# Adafruit_PCA9685_rev_C.net
KiCad netlist of a schematic drawn in EAGLE
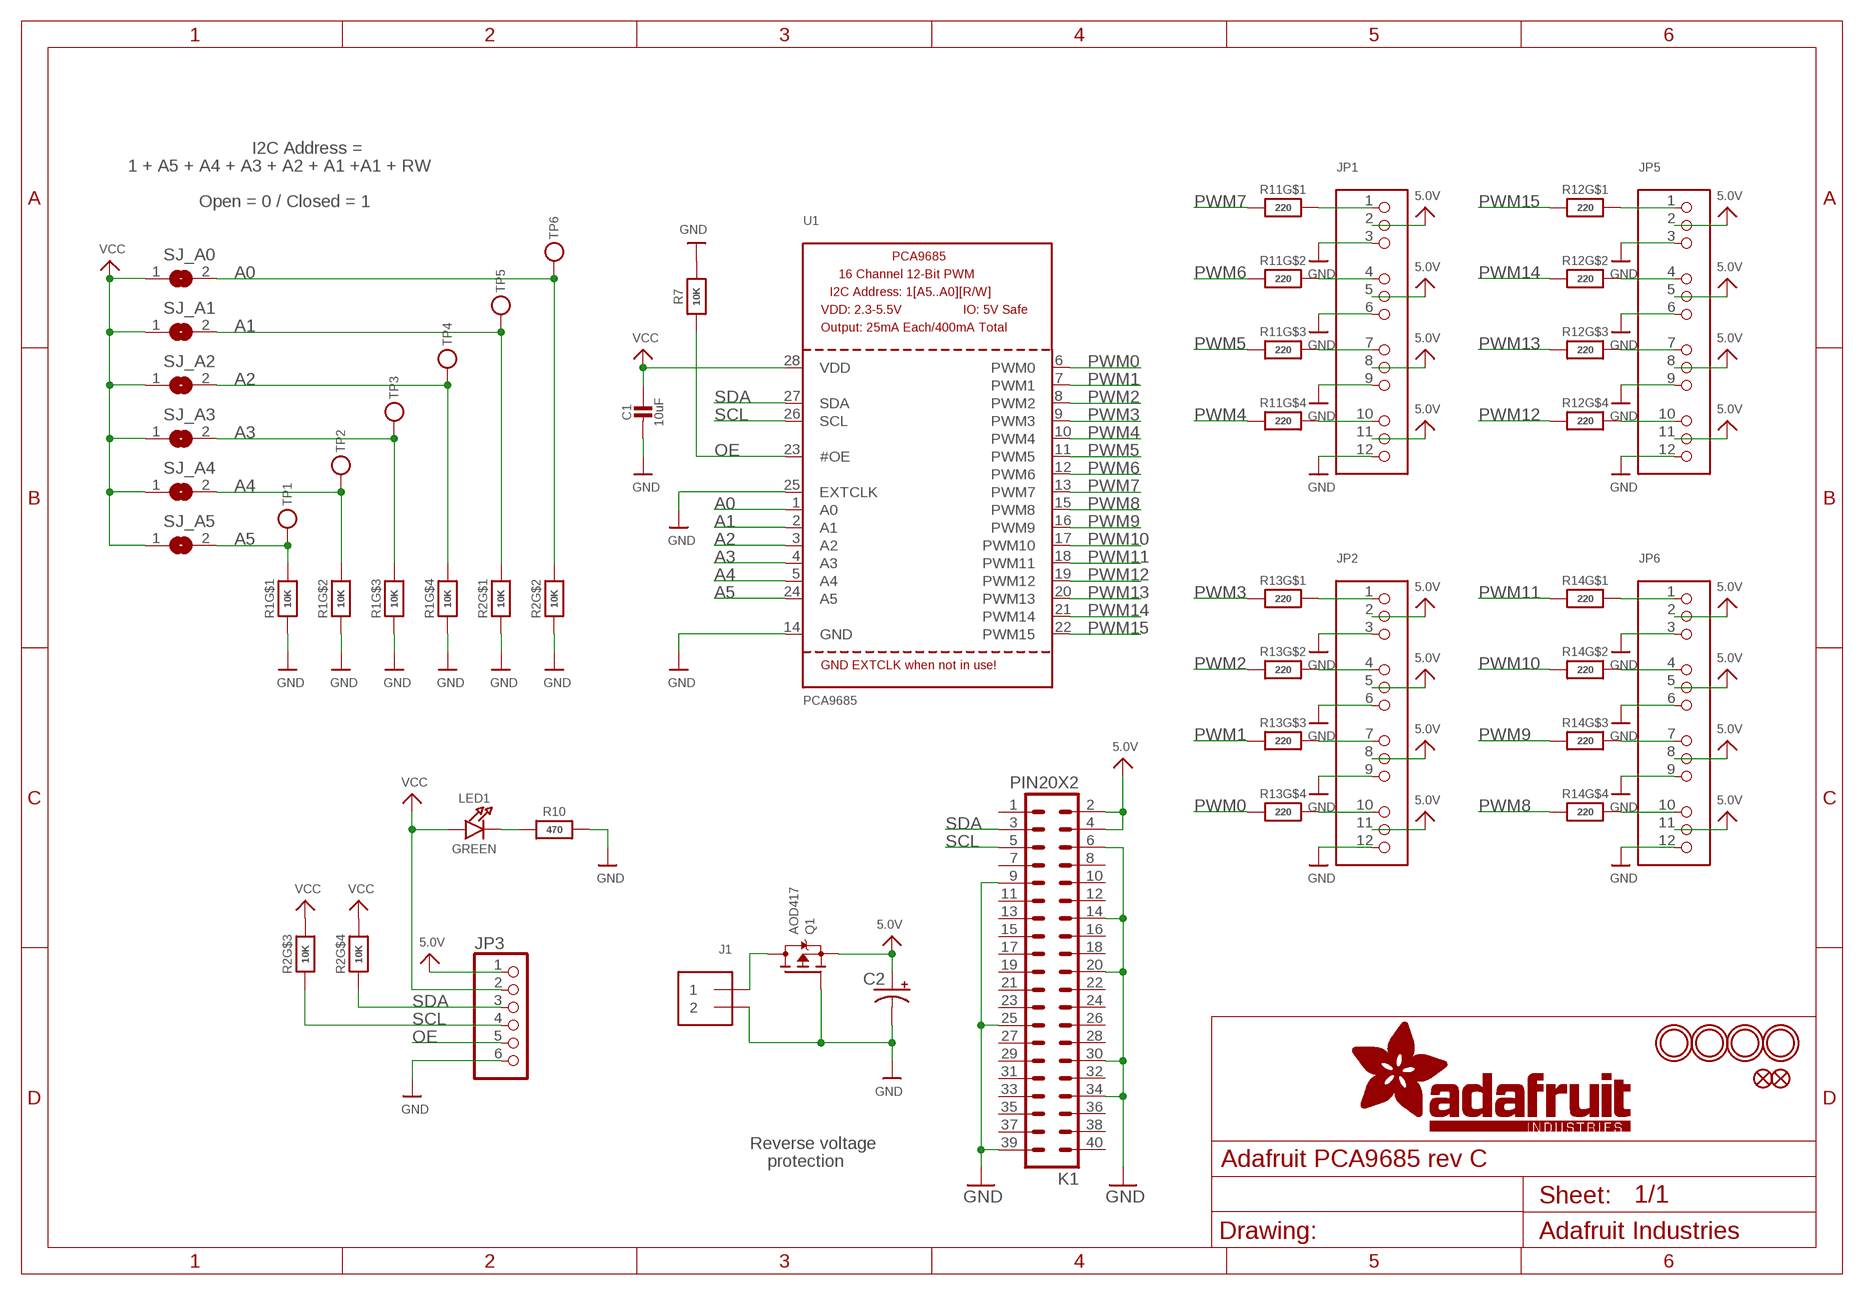
[diagram p0: schematic, sheet 1]

(export (version "E")
  (design (tool "Eeschema 10.0.6"))
  (components
    (comp (ref "C1")
      (value "10uF")
      (footprint "eagle-import:0805-NO")
      (libsource (lib "eagle-import") (part "CAP_CERAMIC0805-NOOUTLINE"))
    )
    (comp (ref "C2")
      (value "CPOL-USE3.5-8")
      (footprint "eagle-import:E3,5-8")
      (libsource (lib "eagle-import") (part "CPOL-USE3.5-8"))
    )
    (comp (ref "FID1")
      (value "FIDUCIAL\"\"")
      (footprint "eagle-import:FIDUCIAL_1MM")
      (libsource (lib "eagle-import") (part "FIDUCIAL{dblquote}{dblquote}"))
    )
    (comp (ref "FID2")
      (value "FIDUCIAL\"\"")
      (footprint "eagle-import:FIDUCIAL_1MM")
      (libsource (lib "eagle-import") (part "FIDUCIAL{dblquote}{dblquote}"))
    )
    (comp (ref "J1")
      (value "TERMBLOCK_1X2")
      (footprint "eagle-import:TERMBLOCK_1X2-3.5MM")
      (libsource (lib "eagle-import") (part "TERMBLOCK_1X2"))
    )
    (comp (ref "JP1")
      (value "HEADER-3X04")
      (footprint "eagle-import:3X04")
      (libsource (lib "eagle-import") (part "HEADER-3X04"))
    )
    (comp (ref "JP2")
      (value "HEADER-3X04")
      (footprint "eagle-import:3X04")
      (libsource (lib "eagle-import") (part "HEADER-3X04"))
    )
    (comp (ref "JP3")
      (value "PINHD-1X6CB")
      (footprint "eagle-import:1X06-CLEANBIG")
      (libsource (lib "eagle-import") (part "PINHD-1X6CB"))
    )
    (comp (ref "JP5")
      (value "HEADER-3X04")
      (footprint "eagle-import:3X04")
      (libsource (lib "eagle-import") (part "HEADER-3X04"))
    )
    (comp (ref "JP6")
      (value "HEADER-3X04")
      (footprint "eagle-import:3X04")
      (libsource (lib "eagle-import") (part "HEADER-3X04"))
    )
    (comp (ref "K1")
      (value "PIN20X2")
      (footprint "eagle-import:PIN_20X2")
      (libsource (lib "eagle-import") (part "PIN20X2"))
    )
    (comp (ref "LED1")
      (value "GREEN")
      (footprint "eagle-import:CHIPLED_0805_NOOUTLINE")
      (libsource (lib "eagle-import") (part "LED0805_NOOUTLINE"))
    )
    (comp (ref "Q1")
      (value "AOD417")
      (footprint "eagle-import:TO252")
      (libsource (lib "eagle-import") (part "MOSFET-PTO252"))
    )
    (comp (ref "R1")
      (value "10K")
      (footprint "eagle-import:RESPACK_4X0603")
      (libsource (lib "eagle-import") (part "RESISTOR_4PACK"))
    )
    (comp (ref "R2")
      (value "10K")
      (footprint "eagle-import:RESPACK_4X0603")
      (libsource (lib "eagle-import") (part "RESISTOR_4PACK"))
    )
    (comp (ref "R7")
      (value "10K")
      (footprint "eagle-import:0805-NO")
      (libsource (lib "eagle-import") (part "RESISTOR0805_NOOUTLINE"))
    )
    (comp (ref "R10")
      (value "470")
      (footprint "eagle-import:_0805MP")
      (libsource (lib "eagle-import") (part "RESISTOR_0805MP"))
    )
    (comp (ref "R11")
      (value "220")
      (footprint "eagle-import:RESPACK_4X0603")
      (libsource (lib "eagle-import") (part "RESISTOR_4PACK"))
    )
    (comp (ref "R12")
      (value "220")
      (footprint "eagle-import:RESPACK_4X0603")
      (libsource (lib "eagle-import") (part "RESISTOR_4PACK"))
    )
    (comp (ref "R13")
      (value "220")
      (footprint "eagle-import:RESPACK_4X0603")
      (libsource (lib "eagle-import") (part "RESISTOR_4PACK"))
    )
    (comp (ref "R14")
      (value "220")
      (footprint "eagle-import:RESPACK_4X0603")
      (libsource (lib "eagle-import") (part "RESISTOR_4PACK"))
    )
    (comp (ref "SJ_A0")
      (value "SOLDERJUMPERREFLOW_NOPASTE")
      (footprint "eagle-import:SOLDERJUMPER_REFLOW_NOPASTE")
      (libsource (lib "eagle-import") (part "SOLDERJUMPERREFLOW_NOPASTE"))
    )
    (comp (ref "SJ_A1")
      (value "SOLDERJUMPERREFLOW_NOPASTE")
      (footprint "eagle-import:SOLDERJUMPER_REFLOW_NOPASTE")
      (libsource (lib "eagle-import") (part "SOLDERJUMPERREFLOW_NOPASTE"))
    )
    (comp (ref "SJ_A2")
      (value "SOLDERJUMPERREFLOW_NOPASTE")
      (footprint "eagle-import:SOLDERJUMPER_REFLOW_NOPASTE")
      (libsource (lib "eagle-import") (part "SOLDERJUMPERREFLOW_NOPASTE"))
    )
    (comp (ref "SJ_A3")
      (value "SOLDERJUMPERREFLOW_NOPASTE")
      (footprint "eagle-import:SOLDERJUMPER_REFLOW_NOPASTE")
      (libsource (lib "eagle-import") (part "SOLDERJUMPERREFLOW_NOPASTE"))
    )
    (comp (ref "SJ_A4")
      (value "SOLDERJUMPERREFLOW_NOPASTE")
      (footprint "eagle-import:SOLDERJUMPER_REFLOW_NOPASTE")
      (libsource (lib "eagle-import") (part "SOLDERJUMPERREFLOW_NOPASTE"))
    )
    (comp (ref "SJ_A5")
      (value "SOLDERJUMPERREFLOW_NOPASTE")
      (footprint "eagle-import:SOLDERJUMPER_REFLOW_NOPASTE")
      (libsource (lib "eagle-import") (part "SOLDERJUMPERREFLOW_NOPASTE"))
    )
    (comp (ref "TP1")
      (value "TESTPOINTROUND1MM")
      (footprint "eagle-import:TESTPOINT_ROUND_1MM")
      (libsource (lib "eagle-import") (part "TESTPOINTROUND1MM"))
    )
    (comp (ref "TP2")
      (value "TESTPOINTROUND1MM")
      (footprint "eagle-import:TESTPOINT_ROUND_1MM")
      (libsource (lib "eagle-import") (part "TESTPOINTROUND1MM"))
    )
    (comp (ref "TP3")
      (value "TESTPOINTROUND1MM")
      (footprint "eagle-import:TESTPOINT_ROUND_1MM")
      (libsource (lib "eagle-import") (part "TESTPOINTROUND1MM"))
    )
    (comp (ref "TP4")
      (value "TESTPOINTROUND1MM")
      (footprint "eagle-import:TESTPOINT_ROUND_1MM")
      (libsource (lib "eagle-import") (part "TESTPOINTROUND1MM"))
    )
    (comp (ref "TP5")
      (value "TESTPOINTROUND1MM")
      (footprint "eagle-import:TESTPOINT_ROUND_1MM")
      (libsource (lib "eagle-import") (part "TESTPOINTROUND1MM"))
    )
    (comp (ref "TP6")
      (value "TESTPOINTROUND1MM")
      (footprint "eagle-import:TESTPOINT_ROUND_1MM")
      (libsource (lib "eagle-import") (part "TESTPOINTROUND1MM"))
    )
    (comp (ref "U$47")
      (value "MOUNTINGHOLE2.5")
      (footprint "eagle-import:MOUNTINGHOLE_2.5_PLATED")
      (libsource (lib "eagle-import") (part "MOUNTINGHOLE2.5"))
    )
    (comp (ref "U$48")
      (value "MOUNTINGHOLE2.5")
      (footprint "eagle-import:MOUNTINGHOLE_2.5_PLATED")
      (libsource (lib "eagle-import") (part "MOUNTINGHOLE2.5"))
    )
    (comp (ref "U$49")
      (value "MOUNTINGHOLE2.5")
      (footprint "eagle-import:MOUNTINGHOLE_2.5_PLATED")
      (libsource (lib "eagle-import") (part "MOUNTINGHOLE2.5"))
    )
    (comp (ref "U$50")
      (value "MOUNTINGHOLE2.5")
      (footprint "eagle-import:MOUNTINGHOLE_2.5_PLATED")
      (libsource (lib "eagle-import") (part "MOUNTINGHOLE2.5"))
    )
    (comp (ref "U1")
      (value "PCA9685")
      (footprint "eagle-import:TSSOP28")
      (libsource (lib "eagle-import") (part "PCA9685"))
    )
  )
  (nets
    (net (code "1") (name "/A0") (class "Default")
      (node (ref "R2") (pin "7") (pinfunction "2_7") (pintype "passive"))
      (node (ref "SJ_A0") (pin "2") (pinfunction "2_2") (pintype "passive"))
      (node (ref "TP6") (pin "P$1") (pinfunction "P$1_P$1") (pintype "bidirectional"))
      (node (ref "U1") (pin "1") (pinfunction "A0_1") (pintype "bidirectional"))
    )
    (net (code "2") (name "/A1") (class "Default")
      (node (ref "R2") (pin "8") (pinfunction "2_8") (pintype "passive"))
      (node (ref "SJ_A1") (pin "2") (pinfunction "2_2") (pintype "passive"))
      (node (ref "TP5") (pin "P$1") (pinfunction "P$1_P$1") (pintype "bidirectional"))
      (node (ref "U1") (pin "2") (pinfunction "A1_2") (pintype "bidirectional"))
    )
    (net (code "3") (name "/A2") (class "Default")
      (node (ref "R1") (pin "5") (pinfunction "2_5") (pintype "passive"))
      (node (ref "SJ_A2") (pin "2") (pinfunction "2_2") (pintype "passive"))
      (node (ref "TP4") (pin "P$1") (pinfunction "P$1_P$1") (pintype "bidirectional"))
      (node (ref "U1") (pin "3") (pinfunction "A2_3") (pintype "bidirectional"))
    )
    (net (code "4") (name "/A3") (class "Default")
      (node (ref "R1") (pin "6") (pinfunction "2_6") (pintype "passive"))
      (node (ref "SJ_A3") (pin "2") (pinfunction "2_2") (pintype "passive"))
      (node (ref "TP3") (pin "P$1") (pinfunction "P$1_P$1") (pintype "bidirectional"))
      (node (ref "U1") (pin "4") (pinfunction "A3_4") (pintype "bidirectional"))
    )
    (net (code "5") (name "/A4") (class "Default")
      (node (ref "R1") (pin "7") (pinfunction "2_7") (pintype "passive"))
      (node (ref "SJ_A4") (pin "2") (pinfunction "2_2") (pintype "passive"))
      (node (ref "TP2") (pin "P$1") (pinfunction "P$1_P$1") (pintype "bidirectional"))
      (node (ref "U1") (pin "5") (pinfunction "A4_5") (pintype "bidirectional"))
    )
    (net (code "6") (name "/A5") (class "Default")
      (node (ref "R1") (pin "8") (pinfunction "2_8") (pintype "passive"))
      (node (ref "SJ_A5") (pin "2") (pinfunction "2_2") (pintype "passive"))
      (node (ref "TP1") (pin "P$1") (pinfunction "P$1_P$1") (pintype "bidirectional"))
      (node (ref "U1") (pin "24") (pinfunction "A5_24") (pintype "bidirectional"))
    )
    (net (code "7") (name "/OE") (class "Default")
      (node (ref "JP3") (pin "5") (pinfunction "5_5") (pintype "passive"))
      (node (ref "R7") (pin "1") (pinfunction "1_1") (pintype "passive"))
      (node (ref "U1") (pin "23") (pinfunction "#OE_23") (pintype "input"))
    )
    (net (code "8") (name "/PWM0") (class "Default")
      (node (ref "R13") (pin "4") (pinfunction "1_4") (pintype "passive"))
      (node (ref "U1") (pin "6") (pinfunction "PWM0_6") (pintype "output"))
    )
    (net (code "9") (name "/PWM1") (class "Default")
      (node (ref "R13") (pin "3") (pinfunction "1_3") (pintype "passive"))
      (node (ref "U1") (pin "7") (pinfunction "PWM1_7") (pintype "output"))
    )
    (net (code "10") (name "/PWM2") (class "Default")
      (node (ref "R13") (pin "2") (pinfunction "1_2") (pintype "passive"))
      (node (ref "U1") (pin "8") (pinfunction "PWM2_8") (pintype "output"))
    )
    (net (code "11") (name "/PWM3") (class "Default")
      (node (ref "R13") (pin "1") (pinfunction "1_1") (pintype "passive"))
      (node (ref "U1") (pin "9") (pinfunction "PWM3_9") (pintype "output"))
    )
    (net (code "12") (name "/PWM4") (class "Default")
      (node (ref "R11") (pin "4") (pinfunction "1_4") (pintype "passive"))
      (node (ref "U1") (pin "10") (pinfunction "PWM4_10") (pintype "output"))
    )
    (net (code "13") (name "/PWM5") (class "Default")
      (node (ref "R11") (pin "3") (pinfunction "1_3") (pintype "passive"))
      (node (ref "U1") (pin "11") (pinfunction "PWM5_11") (pintype "output"))
    )
    (net (code "14") (name "/PWM6") (class "Default")
      (node (ref "R11") (pin "2") (pinfunction "1_2") (pintype "passive"))
      (node (ref "U1") (pin "12") (pinfunction "PWM6_12") (pintype "output"))
    )
    (net (code "15") (name "/PWM7") (class "Default")
      (node (ref "R11") (pin "1") (pinfunction "1_1") (pintype "passive"))
      (node (ref "U1") (pin "13") (pinfunction "PWM7_13") (pintype "output"))
    )
    (net (code "16") (name "/PWM8") (class "Default")
      (node (ref "R14") (pin "4") (pinfunction "1_4") (pintype "passive"))
      (node (ref "U1") (pin "15") (pinfunction "PWM8_15") (pintype "output"))
    )
    (net (code "17") (name "/PWM9") (class "Default")
      (node (ref "R14") (pin "3") (pinfunction "1_3") (pintype "passive"))
      (node (ref "U1") (pin "16") (pinfunction "PWM9_16") (pintype "output"))
    )
    (net (code "18") (name "/PWM10") (class "Default")
      (node (ref "R14") (pin "2") (pinfunction "1_2") (pintype "passive"))
      (node (ref "U1") (pin "17") (pinfunction "PWM10_17") (pintype "output"))
    )
    (net (code "19") (name "/PWM11") (class "Default")
      (node (ref "R14") (pin "1") (pinfunction "1_1") (pintype "passive"))
      (node (ref "U1") (pin "18") (pinfunction "PWM11_18") (pintype "output"))
    )
    (net (code "20") (name "/PWM12") (class "Default")
      (node (ref "R12") (pin "4") (pinfunction "1_4") (pintype "passive"))
      (node (ref "U1") (pin "19") (pinfunction "PWM12_19") (pintype "output"))
    )
    (net (code "21") (name "/PWM13") (class "Default")
      (node (ref "R12") (pin "3") (pinfunction "1_3") (pintype "passive"))
      (node (ref "U1") (pin "20") (pinfunction "PWM13_20") (pintype "output"))
    )
    (net (code "22") (name "/PWM14") (class "Default")
      (node (ref "R12") (pin "2") (pinfunction "1_2") (pintype "passive"))
      (node (ref "U1") (pin "21") (pinfunction "PWM14_21") (pintype "output"))
    )
    (net (code "23") (name "/PWM15") (class "Default")
      (node (ref "R12") (pin "1") (pinfunction "1_1") (pintype "passive"))
      (node (ref "U1") (pin "22") (pinfunction "PWM15_22") (pintype "output"))
    )
    (net (code "24") (name "/SCL") (class "Default")
      (node (ref "JP3") (pin "4") (pinfunction "4_4") (pintype "passive"))
      (node (ref "K1") (pin "5") (pinfunction "5_5") (pintype "passive"))
      (node (ref "R2") (pin "3") (pinfunction "1_3") (pintype "passive"))
      (node (ref "U1") (pin "26") (pinfunction "SCL_26") (pintype "bidirectional"))
    )
    (net (code "25") (name "/SDA") (class "Default")
      (node (ref "JP3") (pin "3") (pinfunction "3_3") (pintype "passive"))
      (node (ref "K1") (pin "3") (pinfunction "3_3") (pintype "passive"))
      (node (ref "R2") (pin "4") (pinfunction "1_4") (pintype "passive"))
      (node (ref "U1") (pin "27") (pinfunction "SDA_27") (pintype "bidirectional"))
    )
    (net (code "26") (name "5.0V") (class "Default")
      (node (ref "C2") (pin "+") (pinfunction "+_+") (pintype "passive"))
      (node (ref "JP1") (pin "11") (pinfunction "11_11") (pintype "passive"))
      (node (ref "JP1") (pin "2") (pinfunction "2_2") (pintype "passive"))
      (node (ref "JP1") (pin "5") (pinfunction "5_5") (pintype "passive"))
      (node (ref "JP1") (pin "8") (pinfunction "8_8") (pintype "passive"))
      (node (ref "JP2") (pin "11") (pinfunction "11_11") (pintype "passive"))
      (node (ref "JP2") (pin "2") (pinfunction "2_2") (pintype "passive"))
      (node (ref "JP2") (pin "5") (pinfunction "5_5") (pintype "passive"))
      (node (ref "JP2") (pin "8") (pinfunction "8_8") (pintype "passive"))
      (node (ref "JP3") (pin "1") (pinfunction "1_1") (pintype "passive"))
      (node (ref "JP5") (pin "11") (pinfunction "11_11") (pintype "passive"))
      (node (ref "JP5") (pin "2") (pinfunction "2_2") (pintype "passive"))
      (node (ref "JP5") (pin "5") (pinfunction "5_5") (pintype "passive"))
      (node (ref "JP5") (pin "8") (pinfunction "8_8") (pintype "passive"))
      (node (ref "JP6") (pin "11") (pinfunction "11_11") (pintype "passive"))
      (node (ref "JP6") (pin "2") (pinfunction "2_2") (pintype "passive"))
      (node (ref "JP6") (pin "5") (pinfunction "5_5") (pintype "passive"))
      (node (ref "JP6") (pin "8") (pinfunction "8_8") (pintype "passive"))
      (node (ref "K1") (pin "2") (pinfunction "2_2") (pintype "passive"))
      (node (ref "K1") (pin "4") (pinfunction "4_4") (pintype "passive"))
      (node (ref "Q1") (pin "2") (pinfunction "S_2") (pintype "passive"))
    )
    (net (code "27") (name "GND") (class "Default")
      (node (ref "C1") (pin "2") (pinfunction "2_2") (pintype "passive"))
      (node (ref "C2") (pin "-") (pinfunction "-_-") (pintype "passive"))
      (node (ref "J1") (pin "2") (pinfunction "2_2") (pintype "passive"))
      (node (ref "JP1") (pin "12") (pinfunction "12_12") (pintype "passive"))
      (node (ref "JP1") (pin "3") (pinfunction "3_3") (pintype "passive"))
      (node (ref "JP1") (pin "6") (pinfunction "6_6") (pintype "passive"))
      (node (ref "JP1") (pin "9") (pinfunction "9_9") (pintype "passive"))
      (node (ref "JP2") (pin "12") (pinfunction "12_12") (pintype "passive"))
      (node (ref "JP2") (pin "3") (pinfunction "3_3") (pintype "passive"))
      (node (ref "JP2") (pin "6") (pinfunction "6_6") (pintype "passive"))
      (node (ref "JP2") (pin "9") (pinfunction "9_9") (pintype "passive"))
      (node (ref "JP3") (pin "6") (pinfunction "6_6") (pintype "passive"))
      (node (ref "JP5") (pin "12") (pinfunction "12_12") (pintype "passive"))
      (node (ref "JP5") (pin "3") (pinfunction "3_3") (pintype "passive"))
      (node (ref "JP5") (pin "6") (pinfunction "6_6") (pintype "passive"))
      (node (ref "JP5") (pin "9") (pinfunction "9_9") (pintype "passive"))
      (node (ref "JP6") (pin "12") (pinfunction "12_12") (pintype "passive"))
      (node (ref "JP6") (pin "3") (pinfunction "3_3") (pintype "passive"))
      (node (ref "JP6") (pin "6") (pinfunction "6_6") (pintype "passive"))
      (node (ref "JP6") (pin "9") (pinfunction "9_9") (pintype "passive"))
      (node (ref "K1") (pin "14") (pinfunction "14_14") (pintype "passive"))
      (node (ref "K1") (pin "20") (pinfunction "20_20") (pintype "passive"))
      (node (ref "K1") (pin "25") (pinfunction "25_25") (pintype "passive"))
      (node (ref "K1") (pin "30") (pinfunction "30_30") (pintype "passive"))
      (node (ref "K1") (pin "34") (pinfunction "34_34") (pintype "passive"))
      (node (ref "K1") (pin "39") (pinfunction "39_39") (pintype "passive"))
      (node (ref "K1") (pin "6") (pinfunction "6_6") (pintype "passive"))
      (node (ref "K1") (pin "9") (pinfunction "9_9") (pintype "passive"))
      (node (ref "Q1") (pin "1") (pinfunction "G_1") (pintype "passive"))
      (node (ref "R1") (pin "1") (pinfunction "1_1") (pintype "passive"))
      (node (ref "R1") (pin "2") (pinfunction "1_2") (pintype "passive"))
      (node (ref "R1") (pin "3") (pinfunction "1_3") (pintype "passive"))
      (node (ref "R1") (pin "4") (pinfunction "1_4") (pintype "passive"))
      (node (ref "R10") (pin "2") (pinfunction "2_2") (pintype "passive"))
      (node (ref "R2") (pin "1") (pinfunction "1_1") (pintype "passive"))
      (node (ref "R2") (pin "2") (pinfunction "1_2") (pintype "passive"))
      (node (ref "R7") (pin "2") (pinfunction "2_2") (pintype "passive"))
      (node (ref "U1") (pin "14") (pinfunction "GND_14") (pintype "power_in"))
      (node (ref "U1") (pin "25") (pinfunction "EXTCLK_25") (pintype "input"))
    )
    (net (code "28") (name "Net-(LED1-PadC)") (class "Default")
      (node (ref "LED1") (pin "C") (pinfunction "C_C") (pintype "passive"))
      (node (ref "R10") (pin "1") (pinfunction "1_1") (pintype "passive"))
    )
    (net (code "29") (name "Net-(Q1-D)") (class "Default")
      (node (ref "J1") (pin "1") (pinfunction "1_1") (pintype "passive"))
      (node (ref "Q1") (pin "3") (pinfunction "D_3") (pintype "passive"))
    )
    (net (code "30") (name "Net-(R11A-2)") (class "Default")
      (node (ref "JP1") (pin "1") (pinfunction "1_1") (pintype "passive"))
      (node (ref "R11") (pin "8") (pinfunction "2_8") (pintype "passive"))
    )
    (net (code "31") (name "Net-(R11B-2)") (class "Default")
      (node (ref "JP1") (pin "4") (pinfunction "4_4") (pintype "passive"))
      (node (ref "R11") (pin "7") (pinfunction "2_7") (pintype "passive"))
    )
    (net (code "32") (name "Net-(R11C-2)") (class "Default")
      (node (ref "JP1") (pin "7") (pinfunction "7_7") (pintype "passive"))
      (node (ref "R11") (pin "6") (pinfunction "2_6") (pintype "passive"))
    )
    (net (code "33") (name "Net-(R11D-2)") (class "Default")
      (node (ref "JP1") (pin "10") (pinfunction "10_10") (pintype "passive"))
      (node (ref "R11") (pin "5") (pinfunction "2_5") (pintype "passive"))
    )
    (net (code "34") (name "Net-(R12A-2)") (class "Default")
      (node (ref "JP5") (pin "1") (pinfunction "1_1") (pintype "passive"))
      (node (ref "R12") (pin "8") (pinfunction "2_8") (pintype "passive"))
    )
    (net (code "35") (name "Net-(R12B-2)") (class "Default")
      (node (ref "JP5") (pin "4") (pinfunction "4_4") (pintype "passive"))
      (node (ref "R12") (pin "7") (pinfunction "2_7") (pintype "passive"))
    )
    (net (code "36") (name "Net-(R12C-2)") (class "Default")
      (node (ref "JP5") (pin "7") (pinfunction "7_7") (pintype "passive"))
      (node (ref "R12") (pin "6") (pinfunction "2_6") (pintype "passive"))
    )
    (net (code "37") (name "Net-(R12D-2)") (class "Default")
      (node (ref "JP5") (pin "10") (pinfunction "10_10") (pintype "passive"))
      (node (ref "R12") (pin "5") (pinfunction "2_5") (pintype "passive"))
    )
    (net (code "38") (name "Net-(R13A-2)") (class "Default")
      (node (ref "JP2") (pin "1") (pinfunction "1_1") (pintype "passive"))
      (node (ref "R13") (pin "8") (pinfunction "2_8") (pintype "passive"))
    )
    (net (code "39") (name "Net-(R13B-2)") (class "Default")
      (node (ref "JP2") (pin "4") (pinfunction "4_4") (pintype "passive"))
      (node (ref "R13") (pin "7") (pinfunction "2_7") (pintype "passive"))
    )
    (net (code "40") (name "Net-(R13C-2)") (class "Default")
      (node (ref "JP2") (pin "7") (pinfunction "7_7") (pintype "passive"))
      (node (ref "R13") (pin "6") (pinfunction "2_6") (pintype "passive"))
    )
    (net (code "41") (name "Net-(R13D-2)") (class "Default")
      (node (ref "JP2") (pin "10") (pinfunction "10_10") (pintype "passive"))
      (node (ref "R13") (pin "5") (pinfunction "2_5") (pintype "passive"))
    )
    (net (code "42") (name "Net-(R14A-2)") (class "Default")
      (node (ref "JP6") (pin "1") (pinfunction "1_1") (pintype "passive"))
      (node (ref "R14") (pin "8") (pinfunction "2_8") (pintype "passive"))
    )
    (net (code "43") (name "Net-(R14B-2)") (class "Default")
      (node (ref "JP6") (pin "4") (pinfunction "4_4") (pintype "passive"))
      (node (ref "R14") (pin "7") (pinfunction "2_7") (pintype "passive"))
    )
    (net (code "44") (name "Net-(R14C-2)") (class "Default")
      (node (ref "JP6") (pin "7") (pinfunction "7_7") (pintype "passive"))
      (node (ref "R14") (pin "6") (pinfunction "2_6") (pintype "passive"))
    )
    (net (code "45") (name "Net-(R14D-2)") (class "Default")
      (node (ref "JP6") (pin "10") (pinfunction "10_10") (pintype "passive"))
      (node (ref "R14") (pin "5") (pinfunction "2_5") (pintype "passive"))
    )
    (net (code "46") (name "VCC") (class "Default")
      (node (ref "C1") (pin "1") (pinfunction "1_1") (pintype "passive"))
      (node (ref "JP3") (pin "2") (pinfunction "2_2") (pintype "passive"))
      (node (ref "LED1") (pin "A") (pinfunction "A_A") (pintype "passive"))
      (node (ref "R2") (pin "5") (pinfunction "2_5") (pintype "passive"))
      (node (ref "R2") (pin "6") (pinfunction "2_6") (pintype "passive"))
      (node (ref "SJ_A0") (pin "1") (pinfunction "1_1") (pintype "passive"))
      (node (ref "SJ_A1") (pin "1") (pinfunction "1_1") (pintype "passive"))
      (node (ref "SJ_A2") (pin "1") (pinfunction "1_1") (pintype "passive"))
      (node (ref "SJ_A3") (pin "1") (pinfunction "1_1") (pintype "passive"))
      (node (ref "SJ_A4") (pin "1") (pinfunction "1_1") (pintype "passive"))
      (node (ref "SJ_A5") (pin "1") (pinfunction "1_1") (pintype "passive"))
      (node (ref "U1") (pin "28") (pinfunction "VDD_28") (pintype "power_in"))
    )
    (net (code "47") (name "unconnected-(K1-Pad1)") (class "Default")
      (node (ref "K1") (pin "1") (pinfunction "1_1") (pintype "passive"))
    )
    (net (code "48") (name "unconnected-(K1-Pad7)") (class "Default")
      (node (ref "K1") (pin "7") (pinfunction "7_7") (pintype "passive"))
    )
    (net (code "49") (name "unconnected-(K1-Pad8)") (class "Default")
      (node (ref "K1") (pin "8") (pinfunction "8_8") (pintype "passive"))
    )
    (net (code "50") (name "unconnected-(K1-Pad10)") (class "Default")
      (node (ref "K1") (pin "10") (pinfunction "10_10") (pintype "passive"))
    )
    (net (code "51") (name "unconnected-(K1-Pad11)") (class "Default")
      (node (ref "K1") (pin "11") (pinfunction "11_11") (pintype "passive"))
    )
    (net (code "52") (name "unconnected-(K1-Pad12)") (class "Default")
      (node (ref "K1") (pin "12") (pinfunction "12_12") (pintype "passive"))
    )
    (net (code "53") (name "unconnected-(K1-Pad13)") (class "Default")
      (node (ref "K1") (pin "13") (pinfunction "13_13") (pintype "passive"))
    )
    (net (code "54") (name "unconnected-(K1-Pad15)") (class "Default")
      (node (ref "K1") (pin "15") (pinfunction "15_15") (pintype "passive"))
    )
    (net (code "55") (name "unconnected-(K1-Pad16)") (class "Default")
      (node (ref "K1") (pin "16") (pinfunction "16_16") (pintype "passive"))
    )
    (net (code "56") (name "unconnected-(K1-Pad17)") (class "Default")
      (node (ref "K1") (pin "17") (pinfunction "17_17") (pintype "passive"))
    )
    (net (code "57") (name "unconnected-(K1-Pad18)") (class "Default")
      (node (ref "K1") (pin "18") (pinfunction "18_18") (pintype "passive"))
    )
    (net (code "58") (name "unconnected-(K1-Pad19)") (class "Default")
      (node (ref "K1") (pin "19") (pinfunction "19_19") (pintype "passive"))
    )
    (net (code "59") (name "unconnected-(K1-Pad21)") (class "Default")
      (node (ref "K1") (pin "21") (pinfunction "21_21") (pintype "passive"))
    )
    (net (code "60") (name "unconnected-(K1-Pad22)") (class "Default")
      (node (ref "K1") (pin "22") (pinfunction "22_22") (pintype "passive"))
    )
    (net (code "61") (name "unconnected-(K1-Pad23)") (class "Default")
      (node (ref "K1") (pin "23") (pinfunction "23_23") (pintype "passive"))
    )
    (net (code "62") (name "unconnected-(K1-Pad24)") (class "Default")
      (node (ref "K1") (pin "24") (pinfunction "24_24") (pintype "passive"))
    )
    (net (code "63") (name "unconnected-(K1-Pad26)") (class "Default")
      (node (ref "K1") (pin "26") (pinfunction "26_26") (pintype "passive"))
    )
    (net (code "64") (name "unconnected-(K1-Pad27)") (class "Default")
      (node (ref "K1") (pin "27") (pinfunction "27_27") (pintype "passive"))
    )
    (net (code "65") (name "unconnected-(K1-Pad28)") (class "Default")
      (node (ref "K1") (pin "28") (pinfunction "28_28") (pintype "passive"))
    )
    (net (code "66") (name "unconnected-(K1-Pad29)") (class "Default")
      (node (ref "K1") (pin "29") (pinfunction "29_29") (pintype "passive"))
    )
    (net (code "67") (name "unconnected-(K1-Pad31)") (class "Default")
      (node (ref "K1") (pin "31") (pinfunction "31_31") (pintype "passive"))
    )
    (net (code "68") (name "unconnected-(K1-Pad32)") (class "Default")
      (node (ref "K1") (pin "32") (pinfunction "32_32") (pintype "passive"))
    )
    (net (code "69") (name "unconnected-(K1-Pad33)") (class "Default")
      (node (ref "K1") (pin "33") (pinfunction "33_33") (pintype "passive"))
    )
    (net (code "70") (name "unconnected-(K1-Pad35)") (class "Default")
      (node (ref "K1") (pin "35") (pinfunction "35_35") (pintype "passive"))
    )
    (net (code "71") (name "unconnected-(K1-Pad36)") (class "Default")
      (node (ref "K1") (pin "36") (pinfunction "36_36") (pintype "passive"))
    )
    (net (code "72") (name "unconnected-(K1-Pad37)") (class "Default")
      (node (ref "K1") (pin "37") (pinfunction "37_37") (pintype "passive"))
    )
    (net (code "73") (name "unconnected-(K1-Pad38)") (class "Default")
      (node (ref "K1") (pin "38") (pinfunction "38_38") (pintype "passive"))
    )
    (net (code "74") (name "unconnected-(K1-Pad40)") (class "Default")
      (node (ref "K1") (pin "40") (pinfunction "40_40") (pintype "passive"))
    )
  )
)
